# Supplies_Pots.net
KiCad netlist of a schematic drawn in Altium Designer
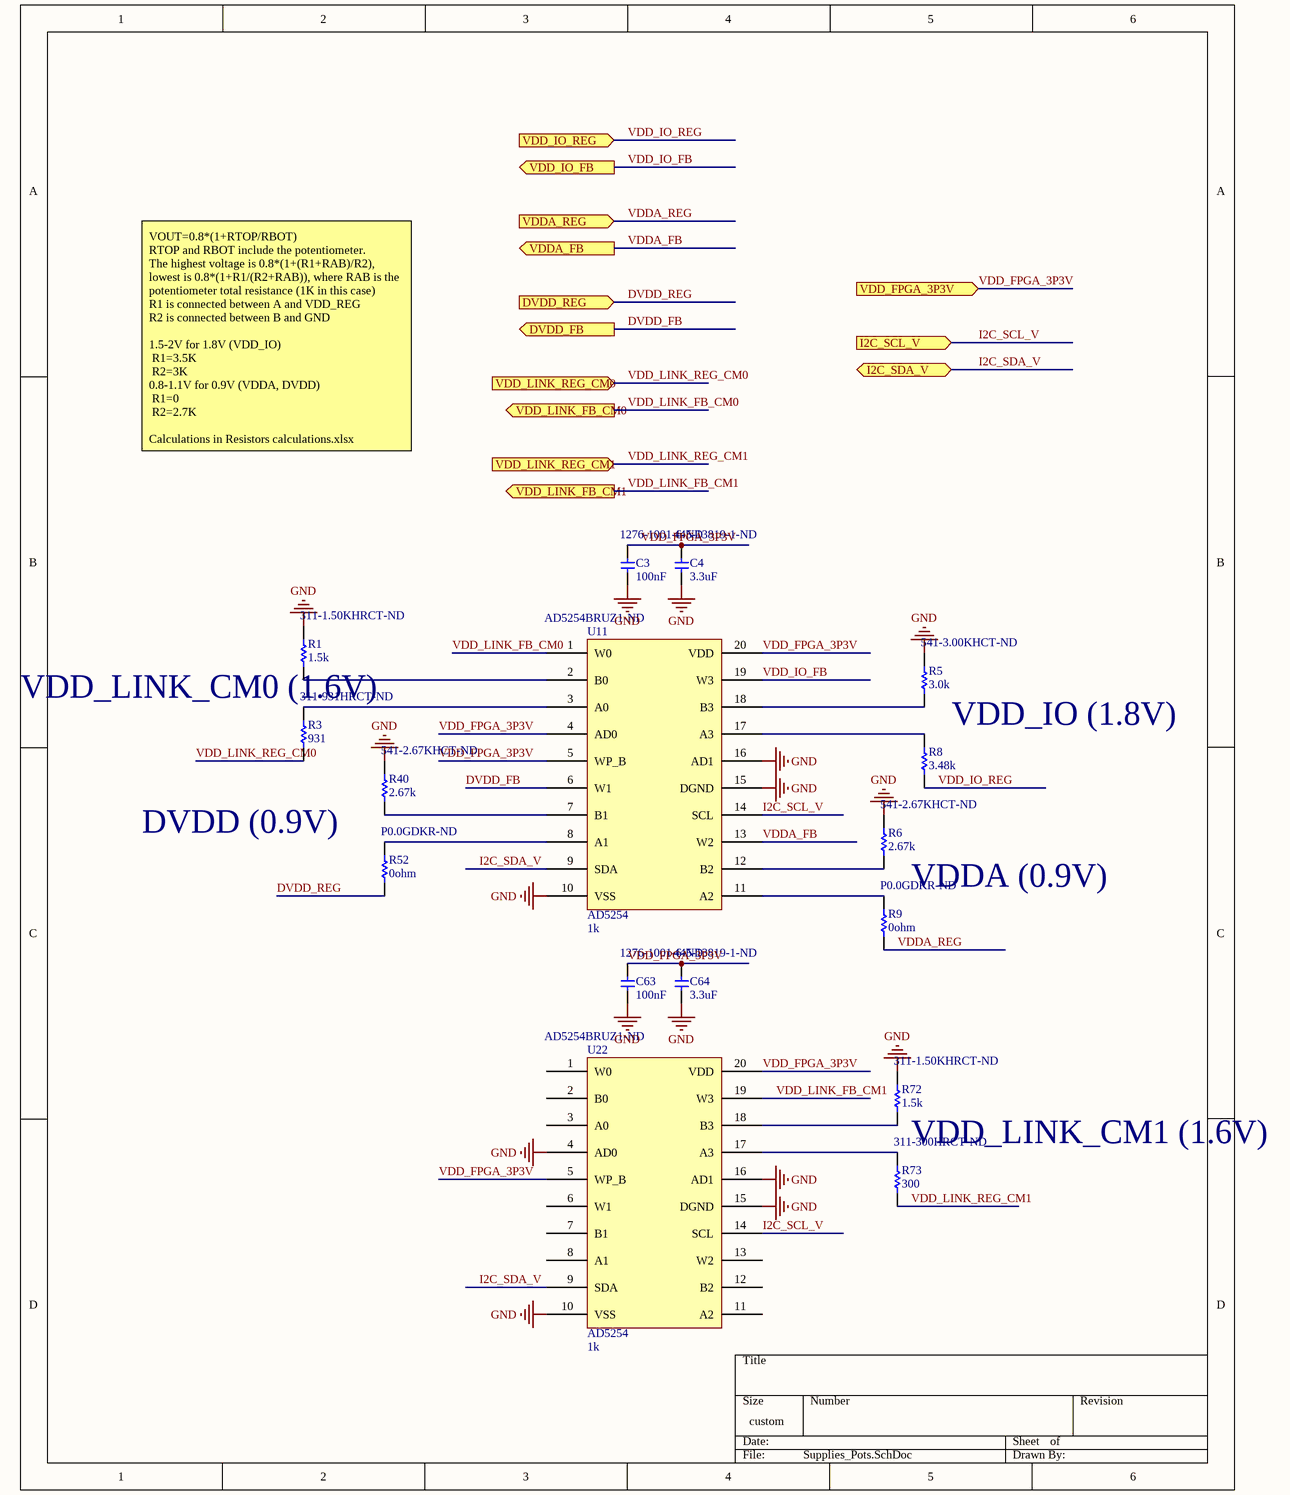
[diagram p0: Supplies_Pots.SchDoc]

(export (version "E")
  (design (tool "Eeschema 10.0.6"))
  (components
    (comp (ref "C3")
      (value "100nF")
      (footprint "CAP_0402")
      (description "CAP CER 0.1uF 10% 16V X7R 0402")
      (fields
        (field (name "MANUFACTURER") "Samsung Electro-Mechanics")
        (field (name "SUPPLIER PART NUMBER 1") "1276-1001-6-ND")
      )
      (libsource (lib "fader2_parts") (part "cap 100nF"))
    )
    (comp (ref "C4")
      (value "3.3uF")
      (footprint "CAP_0402")
      (description "CAP CER 3.3uF 10% 10V X5R 0402")
      (fields (field (name "MANUFACTURER") "TDK") (field (name "SUPPLIER PART NUMBER 1") "445-13819-1-ND"))
      (libsource (lib "fader2_parts") (part "cap 3p3uF"))
    )
    (comp (ref "C63")
      (value "100nF")
      (footprint "CAP_0402")
      (description "CAP CER 0.1uF 10% 16V X7R 0402")
      (fields
        (field (name "MANUFACTURER") "Samsung Electro-Mechanics")
        (field (name "SUPPLIER PART NUMBER 1") "1276-1001-6-ND")
      )
      (libsource (lib "fader2_parts") (part "cap 100nF"))
    )
    (comp (ref "C64")
      (value "3.3uF")
      (footprint "CAP_0402")
      (description "CAP CER 3.3uF 10% 10V X5R 0402")
      (fields (field (name "MANUFACTURER") "TDK") (field (name "SUPPLIER PART NUMBER 1") "445-13819-1-ND"))
      (libsource (lib "fader2_parts") (part "cap 3p3uF"))
    )
    (comp (ref "R1")
      (value "1.5k")
      (footprint "RES_0603")
      (description "RES SMD 1.5K OHM 1% 1/10W 0603")
      (fields (field (name "SUPPLIER PART NUMBER 1") "311-1.50KHRCT-ND"))
      (libsource (lib "fader2_parts") (part "res 1.5 kOhm_1"))
    )
    (comp (ref "R3")
      (value "931")
      (footprint "RES_0603")
      (description "RES SMD 931 OHM 1% 1/10W 0603")
      (fields (field (name "SUPPLIER PART NUMBER 1") "311-931HRCT-ND"))
      (libsource (lib "fader2_parts") (part "res 931 Ohm_1"))
    )
    (comp (ref "R5")
      (value "3.0k")
      (footprint "RES_0603")
      (description "RES SMD 3k OHM 1% 1/10W 0603")
      (fields (field (name "SUPPLIER PART NUMBER 1") "541-3.00KHCT-ND"))
      (libsource (lib "fader2_parts") (part "res 3 kOhm_1"))
    )
    (comp (ref "R6")
      (value "2.67k")
      (footprint "RES_0603")
      (description "RES SMD 2.67kOHM 1% 1/10W 0603")
      (fields (field (name "SUPPLIER PART NUMBER 1") "541-2.67KHCT-ND"))
      (libsource (lib "fader2_parts") (part "res 2.67 Kohm_1"))
    )
    (comp (ref "R8")
      (value "3.48k")
      (footprint "RES_0603")
      (description "RES SMD 3.48kOHM 1% 1/10W 0603")
      (libsource (lib "fader2_parts") (part "res 3.48 kOhm_1"))
    )
    (comp (ref "R9")
      (value "0ohm")
      (footprint "RES_0603")
      (description "RES SMD 0 OHM JUMPER 1/10W 0603")
      (fields (field (name "MANUFACTURER") "Panasonic") (field (name "SUPPLIER PART NUMBER 1") "P0.0GDKR-ND"))
      (libsource (lib "fader2_parts") (part "res 0 ohm 0603"))
    )
    (comp (ref "R40")
      (value "2.67k")
      (footprint "RES_0603")
      (description "RES SMD 2.67kOHM 1% 1/10W 0603")
      (fields (field (name "SUPPLIER PART NUMBER 1") "541-2.67KHCT-ND"))
      (libsource (lib "fader2_parts") (part "res 2.67 Kohm_1"))
    )
    (comp (ref "R52")
      (value "0ohm")
      (footprint "RES_0603")
      (description "RES SMD 0 OHM JUMPER 1/10W 0603")
      (fields (field (name "MANUFACTURER") "Panasonic") (field (name "SUPPLIER PART NUMBER 1") "P0.0GDKR-ND"))
      (libsource (lib "fader2_parts") (part "res 0 ohm 0603"))
    )
    (comp (ref "R72")
      (value "1.5k")
      (footprint "RES_0603")
      (description "RES SMD 1.5K OHM 1% 1/10W 0603")
      (fields (field (name "SUPPLIER PART NUMBER 1") "311-1.50KHRCT-ND"))
      (libsource (lib "fader2_parts") (part "res 1.5 kOhm_1"))
    )
    (comp (ref "R73")
      (value "300")
      (footprint "RES_0603")
      (description "RES SMD 300 OHM 1% 1/10W 0603")
      (fields (field (name "SUPPLIER PART NUMBER 1") "311-300HRCT-ND"))
      (libsource (lib "fader2_parts") (part "res 300 Ohm_1"))
    )
    (comp (ref "U11")
      (value "AD5254")
      (footprint "AD5254")
      (description "Digital Potentiometer 1k Ohm 4 Circuit 256 Taps I²C Interface 20-TSSOP")
      (fields
        (field (name "MANUFACTURER") "Analog Devices")
        (field (name "RESISTANCE") "1k")
        (field (name "SUPPLIER PART NUMBER 1") "AD5254BRUZ1-ND")
      )
      (libsource (lib "fader2_parts") (part "AD5254"))
    )
    (comp (ref "U22")
      (value "AD5254")
      (footprint "AD5254")
      (description "Digital Potentiometer 1k Ohm 4 Circuit 256 Taps I²C Interface 20-TSSOP")
      (fields
        (field (name "MANUFACTURER") "Analog Devices")
        (field (name "RESISTANCE") "1k")
        (field (name "SUPPLIER PART NUMBER 1") "AD5254BRUZ1-ND")
      )
      (libsource (lib "fader2_parts") (part "AD5254"))
    )
  )
  (nets
    (net (code "1") (name "/DVDD_FB") (class "Default")
      (node (ref "U11") (pin "6") (pinfunction "W1_6") (pintype "passive"))
    )
    (net (code "2") (name "/DVDD_REG") (class "Default")
      (node (ref "R52") (pin "2") (pinfunction "BOT_2") (pintype "passive"))
    )
    (net (code "3") (name "/I2C_SCL_V") (class "Default")
      (node (ref "U11") (pin "14") (pinfunction "SCL_14") (pintype "passive"))
      (node (ref "U22") (pin "14") (pinfunction "SCL_14") (pintype "passive"))
    )
    (net (code "4") (name "/I2C_SDA_V") (class "Default")
      (node (ref "U11") (pin "9") (pinfunction "SDA_9") (pintype "passive"))
      (node (ref "U22") (pin "9") (pinfunction "SDA_9") (pintype "passive"))
    )
    (net (code "5") (name "/VDDA_FB") (class "Default")
      (node (ref "U11") (pin "13") (pinfunction "W2_13") (pintype "passive"))
    )
    (net (code "6") (name "/VDDA_REG") (class "Default")
      (node (ref "R9") (pin "2") (pinfunction "BOT_2") (pintype "passive"))
    )
    (net (code "7") (name "/VDD_FPGA_3P3V") (class "Default")
      (node (ref "C3") (pin "1") (pinfunction "1_1") (pintype "passive"))
      (node (ref "C4") (pin "1") (pinfunction "1_1") (pintype "passive"))
      (node (ref "C63") (pin "1") (pinfunction "1_1") (pintype "passive"))
      (node (ref "C64") (pin "1") (pinfunction "1_1") (pintype "passive"))
      (node (ref "U11") (pin "20") (pinfunction "VDD_20") (pintype "passive"))
      (node (ref "U11") (pin "4") (pinfunction "AD0_4") (pintype "passive"))
      (node (ref "U11") (pin "5") (pinfunction "WP_B_5") (pintype "passive"))
      (node (ref "U22") (pin "20") (pinfunction "VDD_20") (pintype "passive"))
      (node (ref "U22") (pin "5") (pinfunction "WP_B_5") (pintype "passive"))
    )
    (net (code "8") (name "/VDD_IO_FB") (class "Default")
      (node (ref "U11") (pin "19") (pinfunction "W3_19") (pintype "passive"))
    )
    (net (code "9") (name "/VDD_IO_REG") (class "Default")
      (node (ref "R8") (pin "2") (pinfunction "BOT_2") (pintype "passive"))
    )
    (net (code "10") (name "/VDD_LINK_FB_CM0") (class "Default")
      (node (ref "U11") (pin "1") (pinfunction "W0_1") (pintype "passive"))
    )
    (net (code "11") (name "/VDD_LINK_FB_CM1") (class "Default")
      (node (ref "U22") (pin "19") (pinfunction "W3_19") (pintype "passive"))
    )
    (net (code "12") (name "/VDD_LINK_REG_CM0") (class "Default")
      (node (ref "R3") (pin "2") (pinfunction "BOT_2") (pintype "passive"))
    )
    (net (code "13") (name "/VDD_LINK_REG_CM1") (class "Default")
      (node (ref "R73") (pin "2") (pinfunction "BOT_2") (pintype "passive"))
    )
    (net (code "14") (name "GND") (class "Default")
      (node (ref "C3") (pin "2") (pinfunction "2_2") (pintype "passive"))
      (node (ref "C4") (pin "2") (pinfunction "2_2") (pintype "passive"))
      (node (ref "C63") (pin "2") (pinfunction "2_2") (pintype "passive"))
      (node (ref "C64") (pin "2") (pinfunction "2_2") (pintype "passive"))
      (node (ref "R1") (pin "1") (pinfunction "TOP_1") (pintype "passive"))
      (node (ref "R40") (pin "1") (pinfunction "TOP_1") (pintype "passive"))
      (node (ref "R5") (pin "1") (pinfunction "TOP_1") (pintype "passive"))
      (node (ref "R6") (pin "1") (pinfunction "TOP_1") (pintype "passive"))
      (node (ref "R72") (pin "1") (pinfunction "TOP_1") (pintype "passive"))
      (node (ref "U11") (pin "10") (pinfunction "VSS_10") (pintype "passive"))
      (node (ref "U11") (pin "15") (pinfunction "DGND_15") (pintype "passive"))
      (node (ref "U11") (pin "16") (pinfunction "AD1_16") (pintype "passive"))
      (node (ref "U22") (pin "10") (pinfunction "VSS_10") (pintype "passive"))
      (node (ref "U22") (pin "15") (pinfunction "DGND_15") (pintype "passive"))
      (node (ref "U22") (pin "16") (pinfunction "AD1_16") (pintype "passive"))
      (node (ref "U22") (pin "4") (pinfunction "AD0_4") (pintype "passive"))
    )
    (net (code "15") (name "Net-(R1-BOT)") (class "Default")
      (node (ref "R1") (pin "2") (pinfunction "BOT_2") (pintype "passive"))
      (node (ref "U11") (pin "2") (pinfunction "B0_2") (pintype "passive"))
    )
    (net (code "16") (name "Net-(R3-TOP)") (class "Default")
      (node (ref "R3") (pin "1") (pinfunction "TOP_1") (pintype "passive"))
      (node (ref "U11") (pin "3") (pinfunction "A0_3") (pintype "passive"))
    )
    (net (code "17") (name "Net-(R5-BOT)") (class "Default")
      (node (ref "R5") (pin "2") (pinfunction "BOT_2") (pintype "passive"))
      (node (ref "U11") (pin "18") (pinfunction "B3_18") (pintype "passive"))
    )
    (net (code "18") (name "Net-(R6-BOT)") (class "Default")
      (node (ref "R6") (pin "2") (pinfunction "BOT_2") (pintype "passive"))
      (node (ref "U11") (pin "12") (pinfunction "B2_12") (pintype "passive"))
    )
    (net (code "19") (name "Net-(R8-TOP)") (class "Default")
      (node (ref "R8") (pin "1") (pinfunction "TOP_1") (pintype "passive"))
      (node (ref "U11") (pin "17") (pinfunction "A3_17") (pintype "passive"))
    )
    (net (code "20") (name "Net-(R9-TOP)") (class "Default")
      (node (ref "R9") (pin "1") (pinfunction "TOP_1") (pintype "passive"))
      (node (ref "U11") (pin "11") (pinfunction "A2_11") (pintype "passive"))
    )
    (net (code "21") (name "Net-(R40-BOT)") (class "Default")
      (node (ref "R40") (pin "2") (pinfunction "BOT_2") (pintype "passive"))
      (node (ref "U11") (pin "7") (pinfunction "B1_7") (pintype "passive"))
    )
    (net (code "22") (name "Net-(R52-TOP)") (class "Default")
      (node (ref "R52") (pin "1") (pinfunction "TOP_1") (pintype "passive"))
      (node (ref "U11") (pin "8") (pinfunction "A1_8") (pintype "passive"))
    )
    (net (code "23") (name "Net-(R72-BOT)") (class "Default")
      (node (ref "R72") (pin "2") (pinfunction "BOT_2") (pintype "passive"))
      (node (ref "U22") (pin "18") (pinfunction "B3_18") (pintype "passive"))
    )
    (net (code "24") (name "Net-(R73-TOP)") (class "Default")
      (node (ref "R73") (pin "1") (pinfunction "TOP_1") (pintype "passive"))
      (node (ref "U22") (pin "17") (pinfunction "A3_17") (pintype "passive"))
    )
    (net (code "25") (name "unconnected-(U22-A0-Pad3)") (class "Default")
      (node (ref "U22") (pin "3") (pinfunction "A0_3") (pintype "passive"))
    )
    (net (code "26") (name "unconnected-(U22-A1-Pad8)") (class "Default")
      (node (ref "U22") (pin "8") (pinfunction "A1_8") (pintype "passive"))
    )
    (net (code "27") (name "unconnected-(U22-A2-Pad11)") (class "Default")
      (node (ref "U22") (pin "11") (pinfunction "A2_11") (pintype "passive"))
    )
    (net (code "28") (name "unconnected-(U22-B0-Pad2)") (class "Default")
      (node (ref "U22") (pin "2") (pinfunction "B0_2") (pintype "passive"))
    )
    (net (code "29") (name "unconnected-(U22-B1-Pad7)") (class "Default")
      (node (ref "U22") (pin "7") (pinfunction "B1_7") (pintype "passive"))
    )
    (net (code "30") (name "unconnected-(U22-B2-Pad12)") (class "Default")
      (node (ref "U22") (pin "12") (pinfunction "B2_12") (pintype "passive"))
    )
    (net (code "31") (name "unconnected-(U22-W0-Pad1)") (class "Default")
      (node (ref "U22") (pin "1") (pinfunction "W0_1") (pintype "passive"))
    )
    (net (code "32") (name "unconnected-(U22-W1-Pad6)") (class "Default")
      (node (ref "U22") (pin "6") (pinfunction "W1_6") (pintype "passive"))
    )
    (net (code "33") (name "unconnected-(U22-W2-Pad13)") (class "Default")
      (node (ref "U22") (pin "13") (pinfunction "W2_13") (pintype "passive"))
    )
  )
)
